# MY_beamControl_R.net
KiCad netlist of a schematic drawn in Altium Designer
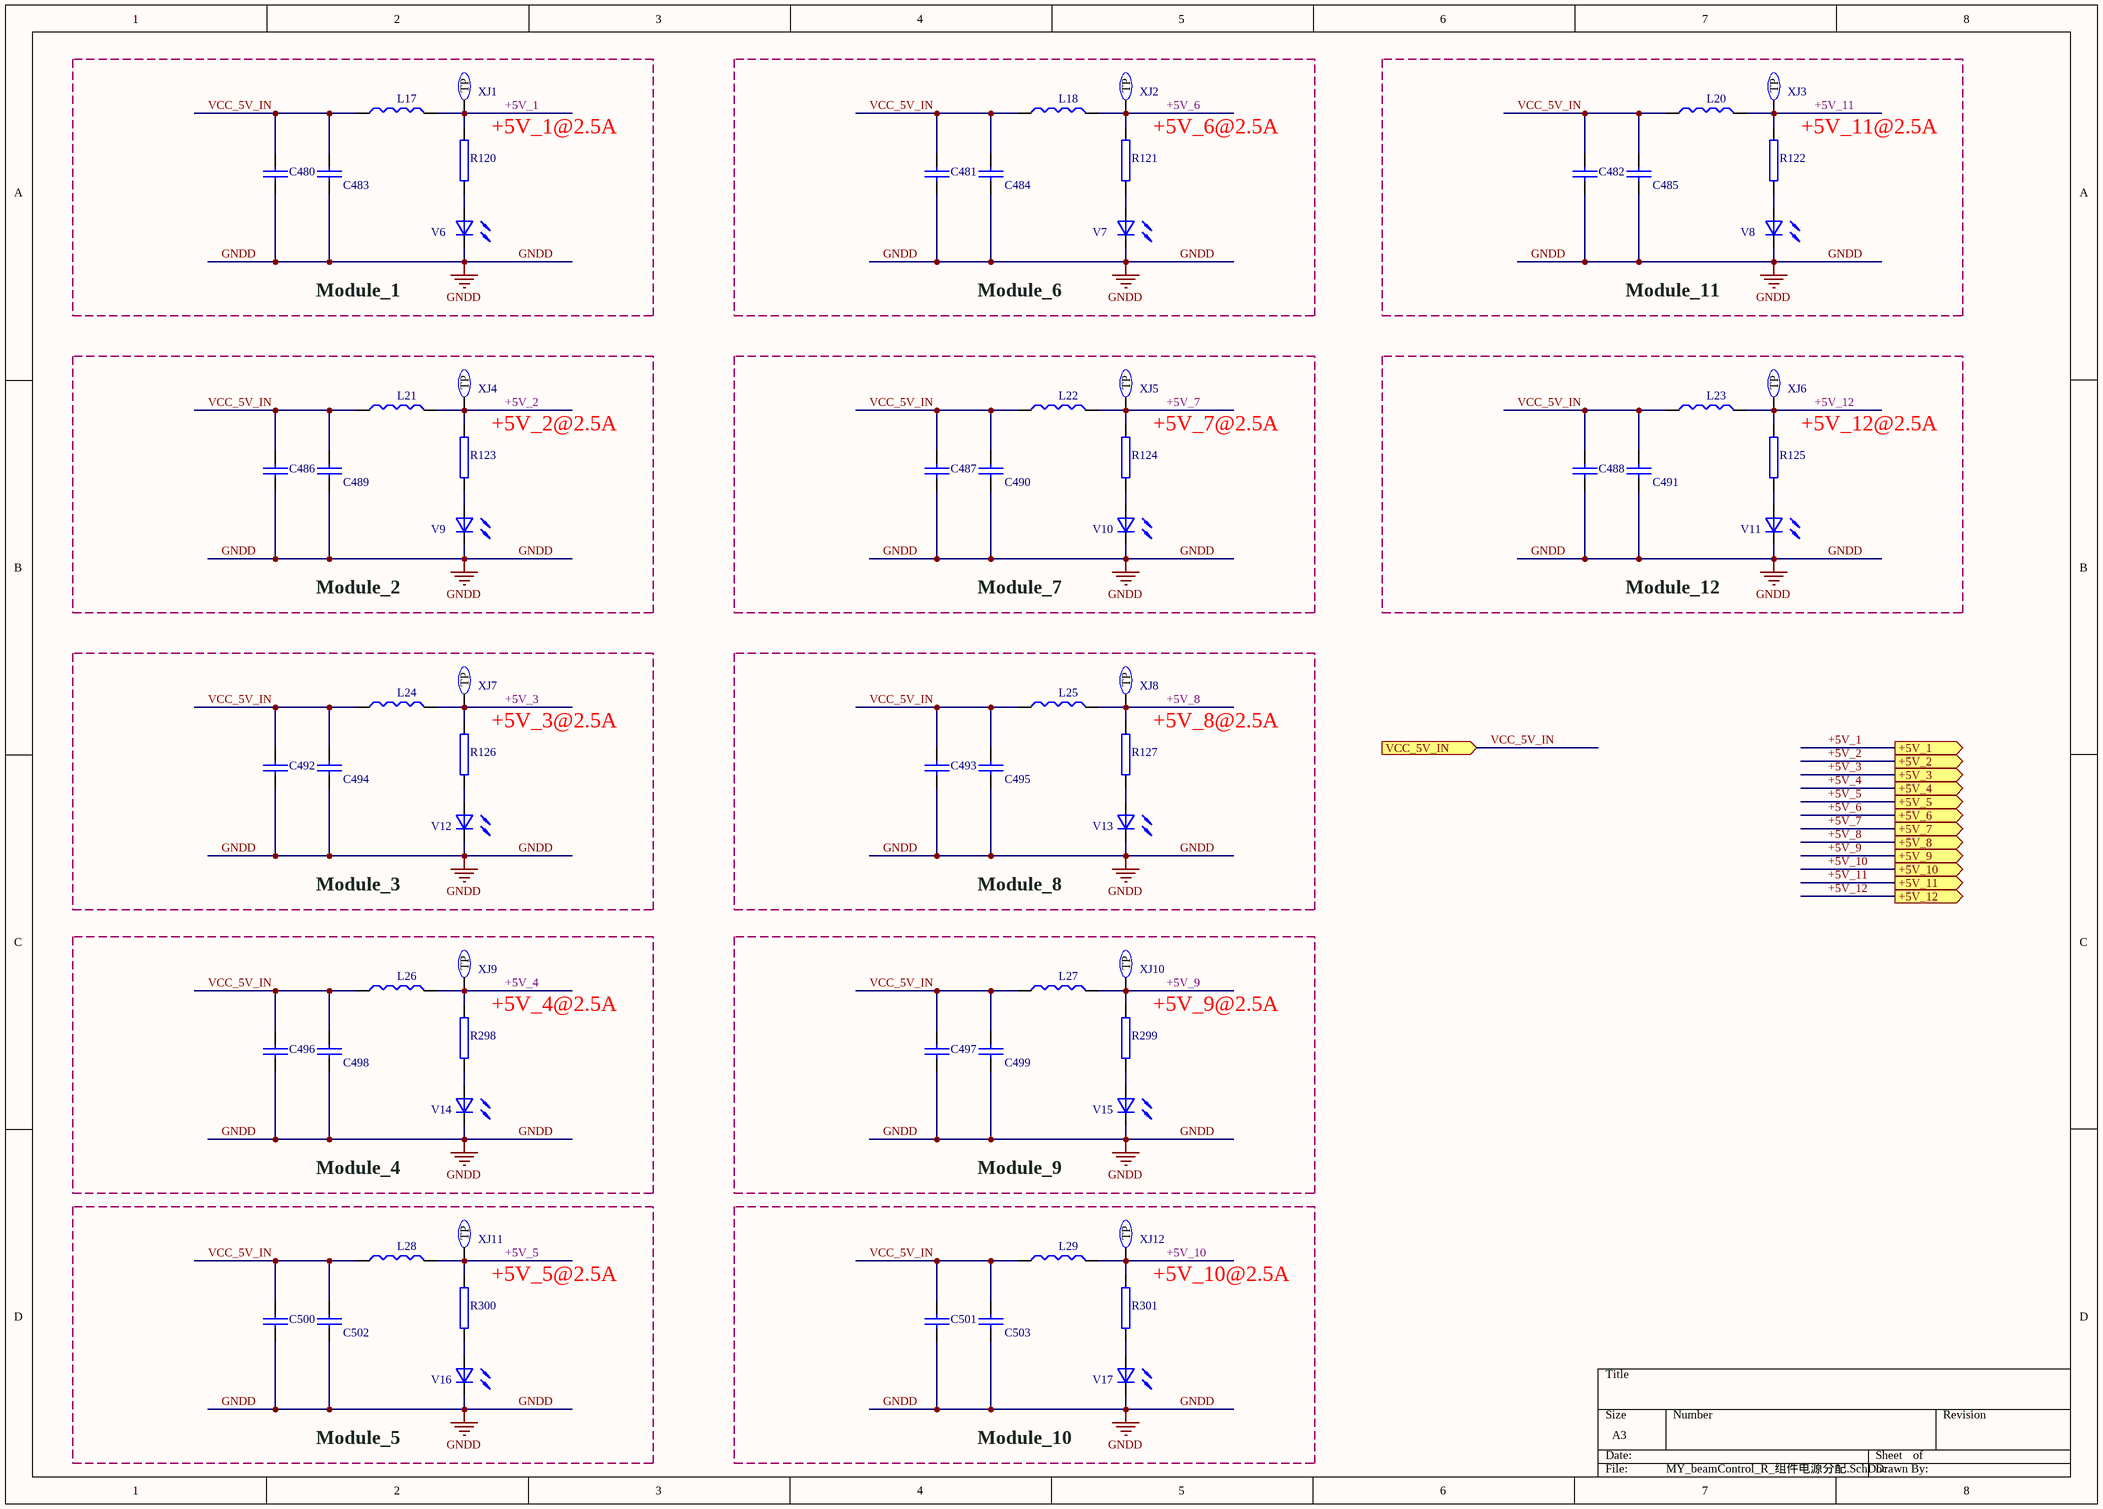
[diagram p0: MY_beamControl_R_组件电源分配.SchDoc]

(export (version "E")
  (design (tool "Eeschema 10.0.6"))
  (components
    (comp (ref "C480") (value "C0805-4.7uF/16V") (footprint "0805") (libsource (lib "mySchLib") (part "C")))
    (comp (ref "C481") (value "C0805-4.7uF/16V") (footprint "0805") (libsource (lib "mySchLib") (part "C")))
    (comp (ref "C482") (value "C0805-4.7uF/16V") (footprint "0805") (libsource (lib "mySchLib") (part "C")))
    (comp (ref "C483")
      (value "CT41-0402-2X1-16V-104(0.1μF)")
      (footprint "c0402")
      (libsource (lib "mySchLib") (part "C_2"))
    )
    (comp (ref "C484")
      (value "CT41-0402-2X1-16V-104(0.1μF)")
      (footprint "c0402")
      (libsource (lib "mySchLib") (part "C_2"))
    )
    (comp (ref "C485")
      (value "CT41-0402-2X1-16V-104(0.1μF)")
      (footprint "c0402")
      (libsource (lib "mySchLib") (part "C_2"))
    )
    (comp (ref "C486") (value "C0805-4.7uF/16V") (footprint "0805") (libsource (lib "mySchLib") (part "C")))
    (comp (ref "C487") (value "C0805-4.7uF/16V") (footprint "0805") (libsource (lib "mySchLib") (part "C")))
    (comp (ref "C488") (value "C0805-4.7uF/16V") (footprint "C0805") (libsource (lib "mySchLib") (part "C")))
    (comp (ref "C489")
      (value "CT41-0402-2X1-16V-104(0.1μF)")
      (footprint "c0402")
      (libsource (lib "mySchLib") (part "C_2"))
    )
    (comp (ref "C490")
      (value "CT41-0402-2X1-16V-104(0.1μF)")
      (footprint "c0402")
      (libsource (lib "mySchLib") (part "C_2"))
    )
    (comp (ref "C491")
      (value "CT41-0402-2X1-16V-104(0.1μF)")
      (footprint "c0402")
      (libsource (lib "mySchLib") (part "C_2"))
    )
    (comp (ref "C492") (value "C0805-4.7uF/16V") (footprint "0805") (libsource (lib "mySchLib") (part "C")))
    (comp (ref "C493") (value "C0805-4.7uF/16V") (footprint "0805") (libsource (lib "mySchLib") (part "C")))
    (comp (ref "C494")
      (value "CT41-0402-2X1-16V-104(0.1μF)")
      (footprint "c0402")
      (libsource (lib "mySchLib") (part "C_2"))
    )
    (comp (ref "C495")
      (value "CT41-0402-2X1-16V-104(0.1μF)")
      (footprint "c0402")
      (libsource (lib "mySchLib") (part "C_2"))
    )
    (comp (ref "C496") (value "C0805-4.7uF/16V") (footprint "0805") (libsource (lib "mySchLib") (part "C")))
    (comp (ref "C497") (value "C0805-4.7uF/16V") (footprint "0805") (libsource (lib "mySchLib") (part "C")))
    (comp (ref "C498")
      (value "CT41-0402-2X1-16V-104(0.1μF)")
      (footprint "c0402")
      (libsource (lib "mySchLib") (part "C_2"))
    )
    (comp (ref "C499")
      (value "CT41-0402-2X1-16V-104(0.1μF)")
      (footprint "c0402")
      (libsource (lib "mySchLib") (part "C_2"))
    )
    (comp (ref "C500") (value "C0805-4.7uF/16V") (footprint "0805") (libsource (lib "mySchLib") (part "C")))
    (comp (ref "C501") (value "C0805-4.7uF/16V") (footprint "0805") (libsource (lib "mySchLib") (part "C")))
    (comp (ref "C502")
      (value "CT41-0402-2X1-16V-104(0.1μF)")
      (footprint "c0402")
      (libsource (lib "mySchLib") (part "C_2"))
    )
    (comp (ref "C503")
      (value "CT41-0402-2X1-16V-104(0.1μF)")
      (footprint "c0402")
      (libsource (lib "mySchLib") (part "C_2"))
    )
    (comp (ref "L17")
      (value "MPZ2012S101A")
      (footprint "R0805")
      (libsource (lib "*") (part "ProE2A0.TMP_UnNamed_1"))
    )
    (comp (ref "L18")
      (value "MPZ2012S101A")
      (footprint "R0805")
      (libsource (lib "*") (part "ProE2A0.TMP_UnNamed_1"))
    )
    (comp (ref "L20")
      (value "MPZ2012S101A")
      (footprint "R0805")
      (libsource (lib "*") (part "ProE2A0.TMP_UnNamed_1"))
    )
    (comp (ref "L21")
      (value "MPZ2012S101A")
      (footprint "R0805")
      (libsource (lib "*") (part "ProE2A0.TMP_UnNamed_1"))
    )
    (comp (ref "L22")
      (value "MPZ2012S101A")
      (footprint "R0805")
      (libsource (lib "*") (part "ProE2A0.TMP_UnNamed_1"))
    )
    (comp (ref "L23")
      (value "MPZ2012S101A")
      (footprint "R0805")
      (libsource (lib "*") (part "ProE2A0.TMP_UnNamed_1"))
    )
    (comp (ref "L24")
      (value "MPZ2012S101A")
      (footprint "R0805")
      (libsource (lib "*") (part "ProE2A0.TMP_UnNamed_1"))
    )
    (comp (ref "L25")
      (value "MPZ2012S101A")
      (footprint "R0805")
      (libsource (lib "*") (part "ProE2A0.TMP_UnNamed_1"))
    )
    (comp (ref "L26")
      (value "MPZ2012S101A")
      (footprint "R0805")
      (libsource (lib "*") (part "ProE2A0.TMP_UnNamed_1"))
    )
    (comp (ref "L27")
      (value "MPZ2012S101A")
      (footprint "R0805")
      (libsource (lib "*") (part "ProE2A0.TMP_UnNamed_1"))
    )
    (comp (ref "L28")
      (value "MPZ2012S101A")
      (footprint "R0805")
      (libsource (lib "*") (part "ProE2A0.TMP_UnNamed_1"))
    )
    (comp (ref "L29")
      (value "MPZ2012S101A")
      (footprint "R0805")
      (libsource (lib "*") (part "ProE2A0.TMP_UnNamed_1"))
    )
    (comp (ref "R120") (value "0805-512(5.1K)") (footprint "0805") (libsource (lib "*") (part "RES2")))
    (comp (ref "R121") (value "0805-512(5.1K)") (footprint "0805") (libsource (lib "*") (part "RES2")))
    (comp (ref "R122") (value "0805-512(5.1K)") (footprint "0805") (libsource (lib "*") (part "RES2")))
    (comp (ref "R123") (value "0805-512(5.1K)") (footprint "0805") (libsource (lib "*") (part "RES2")))
    (comp (ref "R124") (value "0805-512(5.1K)") (footprint "0805") (libsource (lib "*") (part "RES2")))
    (comp (ref "R125") (value "0805-512(5.1K)") (footprint "0805") (libsource (lib "*") (part "RES2")))
    (comp (ref "R126") (value "0805-512(5.1K)") (footprint "0805") (libsource (lib "*") (part "RES2")))
    (comp (ref "R127") (value "0805-512(5.1K)") (footprint "0805") (libsource (lib "*") (part "RES2")))
    (comp (ref "R298") (value "0805-512(5.1K)") (footprint "0805") (libsource (lib "*") (part "RES2")))
    (comp (ref "R299") (value "0805-512(5.1K)") (footprint "0805") (libsource (lib "*") (part "RES2")))
    (comp (ref "R300") (value "0805-512(5.1K)") (footprint "0805") (libsource (lib "*") (part "RES2")))
    (comp (ref "R301") (value "0805-512(5.1K)") (footprint "0805") (libsource (lib "*") (part "RES2")))
    (comp (ref "V6") (value "LED0603-GREEN") (footprint "LED-R0603") (libsource (lib "*") (part "LED")))
    (comp (ref "V7") (value "LED0603-GREEN") (footprint "LED-R0603") (libsource (lib "*") (part "LED")))
    (comp (ref "V8") (value "LED0603-GREEN") (footprint "LED-R0603") (libsource (lib "*") (part "LED")))
    (comp (ref "V9") (value "LED0603-GREEN") (footprint "LED-R0603") (libsource (lib "*") (part "LED")))
    (comp (ref "V10") (value "LED0603-GREEN") (footprint "LED-R0603") (libsource (lib "*") (part "LED")))
    (comp (ref "V11") (value "LED0603-GREEN") (footprint "LED-R0603") (libsource (lib "*") (part "LED")))
    (comp (ref "V12") (value "LED0603-GREEN") (footprint "LED-R0603") (libsource (lib "*") (part "LED")))
    (comp (ref "V13") (value "LED0603-GREEN") (footprint "LED-R0603") (libsource (lib "*") (part "LED")))
    (comp (ref "V14") (value "LED0603-GREEN") (footprint "LED-R0603") (libsource (lib "*") (part "LED")))
    (comp (ref "V15") (value "LED0603-GREEN") (footprint "LED-R0603") (libsource (lib "*") (part "LED")))
    (comp (ref "V16") (value "LED0603-GREEN") (footprint "LED-R0603") (libsource (lib "*") (part "LED")))
    (comp (ref "V17") (value "LED0603-GREEN") (footprint "LED-R0603") (libsource (lib "*") (part "LED")))
    (comp (ref "XJ1")
      (value "Test Point")
      (footprint "TP3")
      (description "测试点")
      (libsource (lib "mySchLib") (part "TP"))
    )
    (comp (ref "XJ2")
      (value "Test Point")
      (footprint "TP3")
      (description "测试点")
      (libsource (lib "mySchLib") (part "TP"))
    )
    (comp (ref "XJ3")
      (value "Test Point")
      (footprint "TP3")
      (description "测试点")
      (libsource (lib "mySchLib") (part "TP"))
    )
    (comp (ref "XJ4")
      (value "Test Point")
      (footprint "TP3")
      (description "测试点")
      (libsource (lib "mySchLib") (part "TP"))
    )
    (comp (ref "XJ5")
      (value "Test Point")
      (footprint "TP3")
      (description "测试点")
      (libsource (lib "mySchLib") (part "TP"))
    )
    (comp (ref "XJ6")
      (value "Test Point")
      (footprint "TP3")
      (description "测试点")
      (libsource (lib "mySchLib") (part "TP"))
    )
    (comp (ref "XJ7")
      (value "Test Point")
      (footprint "TP3")
      (description "测试点")
      (libsource (lib "mySchLib") (part "TP"))
    )
    (comp (ref "XJ8")
      (value "Test Point")
      (footprint "TP3")
      (description "测试点")
      (libsource (lib "mySchLib") (part "TP"))
    )
    (comp (ref "XJ9")
      (value "Test Point")
      (footprint "TP3")
      (description "测试点")
      (libsource (lib "mySchLib") (part "TP"))
    )
    (comp (ref "XJ10")
      (value "Test Point")
      (footprint "TP3")
      (description "测试点")
      (libsource (lib "mySchLib") (part "TP"))
    )
    (comp (ref "XJ11")
      (value "Test Point")
      (footprint "TP3")
      (description "测试点")
      (libsource (lib "mySchLib") (part "TP"))
    )
    (comp (ref "XJ12")
      (value "Test Point")
      (footprint "TP3")
      (description "测试点")
      (libsource (lib "mySchLib") (part "TP"))
    )
  )
  (nets
    (net (code "1") (name "/+5V_1") (class "Default")
      (node (ref "L17") (pin "2") (pintype "passive"))
      (node (ref "R120") (pin "2") (pintype "passive"))
      (node (ref "XJ1") (pin "1") (pinfunction "TP_1") (pintype "passive"))
    )
    (net (code "2") (name "/+5V_2") (class "Default")
      (node (ref "L21") (pin "2") (pintype "passive"))
      (node (ref "R123") (pin "2") (pintype "passive"))
      (node (ref "XJ4") (pin "1") (pinfunction "TP_1") (pintype "passive"))
    )
    (net (code "3") (name "/+5V_3") (class "Default")
      (node (ref "L24") (pin "2") (pintype "passive"))
      (node (ref "R126") (pin "2") (pintype "passive"))
      (node (ref "XJ7") (pin "1") (pinfunction "TP_1") (pintype "passive"))
    )
    (net (code "4") (name "/+5V_4") (class "Default")
      (node (ref "L26") (pin "2") (pintype "passive"))
      (node (ref "R298") (pin "2") (pintype "passive"))
      (node (ref "XJ9") (pin "1") (pinfunction "TP_1") (pintype "passive"))
    )
    (net (code "5") (name "/+5V_5") (class "Default")
      (node (ref "L28") (pin "2") (pintype "passive"))
      (node (ref "R300") (pin "2") (pintype "passive"))
      (node (ref "XJ11") (pin "1") (pinfunction "TP_1") (pintype "passive"))
    )
    (net (code "6") (name "/+5V_6") (class "Default")
      (node (ref "L18") (pin "2") (pintype "passive"))
      (node (ref "R121") (pin "2") (pintype "passive"))
      (node (ref "XJ2") (pin "1") (pinfunction "TP_1") (pintype "passive"))
    )
    (net (code "7") (name "/+5V_7") (class "Default")
      (node (ref "L22") (pin "2") (pintype "passive"))
      (node (ref "R124") (pin "2") (pintype "passive"))
      (node (ref "XJ5") (pin "1") (pinfunction "TP_1") (pintype "passive"))
    )
    (net (code "8") (name "/+5V_8") (class "Default")
      (node (ref "L25") (pin "2") (pintype "passive"))
      (node (ref "R127") (pin "2") (pintype "passive"))
      (node (ref "XJ8") (pin "1") (pinfunction "TP_1") (pintype "passive"))
    )
    (net (code "9") (name "/+5V_9") (class "Default")
      (node (ref "L27") (pin "2") (pintype "passive"))
      (node (ref "R299") (pin "2") (pintype "passive"))
      (node (ref "XJ10") (pin "1") (pinfunction "TP_1") (pintype "passive"))
    )
    (net (code "10") (name "/+5V_10") (class "Default")
      (node (ref "L29") (pin "2") (pintype "passive"))
      (node (ref "R301") (pin "2") (pintype "passive"))
      (node (ref "XJ12") (pin "1") (pinfunction "TP_1") (pintype "passive"))
    )
    (net (code "11") (name "/+5V_11") (class "Default")
      (node (ref "L20") (pin "2") (pintype "passive"))
      (node (ref "R122") (pin "2") (pintype "passive"))
      (node (ref "XJ3") (pin "1") (pinfunction "TP_1") (pintype "passive"))
    )
    (net (code "12") (name "/+5V_12") (class "Default")
      (node (ref "L23") (pin "2") (pintype "passive"))
      (node (ref "R125") (pin "2") (pintype "passive"))
      (node (ref "XJ6") (pin "1") (pinfunction "TP_1") (pintype "passive"))
    )
    (net (code "13") (name "/VCC_5V_IN") (class "Default")
      (node (ref "C480") (pin "2") (pintype "passive"))
      (node (ref "C481") (pin "2") (pintype "passive"))
      (node (ref "C482") (pin "2") (pintype "passive"))
      (node (ref "C483") (pin "1") (pintype "passive"))
      (node (ref "C484") (pin "1") (pintype "passive"))
      (node (ref "C485") (pin "1") (pintype "passive"))
      (node (ref "C486") (pin "2") (pintype "passive"))
      (node (ref "C487") (pin "2") (pintype "passive"))
      (node (ref "C488") (pin "2") (pintype "passive"))
      (node (ref "C489") (pin "1") (pintype "passive"))
      (node (ref "C490") (pin "1") (pintype "passive"))
      (node (ref "C491") (pin "1") (pintype "passive"))
      (node (ref "C492") (pin "2") (pintype "passive"))
      (node (ref "C493") (pin "2") (pintype "passive"))
      (node (ref "C494") (pin "1") (pintype "passive"))
      (node (ref "C495") (pin "1") (pintype "passive"))
      (node (ref "C496") (pin "2") (pintype "passive"))
      (node (ref "C497") (pin "2") (pintype "passive"))
      (node (ref "C498") (pin "1") (pintype "passive"))
      (node (ref "C499") (pin "1") (pintype "passive"))
      (node (ref "C500") (pin "2") (pintype "passive"))
      (node (ref "C501") (pin "2") (pintype "passive"))
      (node (ref "C502") (pin "1") (pintype "passive"))
      (node (ref "C503") (pin "1") (pintype "passive"))
      (node (ref "L17") (pin "1") (pintype "passive"))
      (node (ref "L18") (pin "1") (pintype "passive"))
      (node (ref "L20") (pin "1") (pintype "passive"))
      (node (ref "L21") (pin "1") (pintype "passive"))
      (node (ref "L22") (pin "1") (pintype "passive"))
      (node (ref "L23") (pin "1") (pintype "passive"))
      (node (ref "L24") (pin "1") (pintype "passive"))
      (node (ref "L25") (pin "1") (pintype "passive"))
      (node (ref "L26") (pin "1") (pintype "passive"))
      (node (ref "L27") (pin "1") (pintype "passive"))
      (node (ref "L28") (pin "1") (pintype "passive"))
      (node (ref "L29") (pin "1") (pintype "passive"))
    )
    (net (code "14") (name "GNDD") (class "Default")
      (node (ref "C480") (pin "1") (pintype "passive"))
      (node (ref "C481") (pin "1") (pintype "passive"))
      (node (ref "C482") (pin "1") (pintype "passive"))
      (node (ref "C483") (pin "2") (pintype "passive"))
      (node (ref "C484") (pin "2") (pintype "passive"))
      (node (ref "C485") (pin "2") (pintype "passive"))
      (node (ref "C486") (pin "1") (pintype "passive"))
      (node (ref "C487") (pin "1") (pintype "passive"))
      (node (ref "C488") (pin "1") (pintype "passive"))
      (node (ref "C489") (pin "2") (pintype "passive"))
      (node (ref "C490") (pin "2") (pintype "passive"))
      (node (ref "C491") (pin "2") (pintype "passive"))
      (node (ref "C492") (pin "1") (pintype "passive"))
      (node (ref "C493") (pin "1") (pintype "passive"))
      (node (ref "C494") (pin "2") (pintype "passive"))
      (node (ref "C495") (pin "2") (pintype "passive"))
      (node (ref "C496") (pin "1") (pintype "passive"))
      (node (ref "C497") (pin "1") (pintype "passive"))
      (node (ref "C498") (pin "2") (pintype "passive"))
      (node (ref "C499") (pin "2") (pintype "passive"))
      (node (ref "C500") (pin "1") (pintype "passive"))
      (node (ref "C501") (pin "1") (pintype "passive"))
      (node (ref "C502") (pin "2") (pintype "passive"))
      (node (ref "C503") (pin "2") (pintype "passive"))
      (node (ref "V10") (pin "2") (pinfunction "K_2") (pintype "passive"))
      (node (ref "V11") (pin "2") (pinfunction "K_2") (pintype "passive"))
      (node (ref "V12") (pin "2") (pinfunction "K_2") (pintype "passive"))
      (node (ref "V13") (pin "2") (pinfunction "K_2") (pintype "passive"))
      (node (ref "V14") (pin "2") (pinfunction "K_2") (pintype "passive"))
      (node (ref "V15") (pin "2") (pinfunction "K_2") (pintype "passive"))
      (node (ref "V16") (pin "2") (pinfunction "K_2") (pintype "passive"))
      (node (ref "V17") (pin "2") (pinfunction "K_2") (pintype "passive"))
      (node (ref "V6") (pin "2") (pinfunction "K_2") (pintype "passive"))
      (node (ref "V7") (pin "2") (pinfunction "K_2") (pintype "passive"))
      (node (ref "V8") (pin "2") (pinfunction "K_2") (pintype "passive"))
      (node (ref "V9") (pin "2") (pinfunction "K_2") (pintype "passive"))
    )
    (net (code "15") (name "Net-(V6-A)") (class "Default")
      (node (ref "R120") (pin "1") (pintype "passive"))
      (node (ref "V6") (pin "1") (pinfunction "A_1") (pintype "passive"))
    )
    (net (code "16") (name "Net-(V7-A)") (class "Default")
      (node (ref "R121") (pin "1") (pintype "passive"))
      (node (ref "V7") (pin "1") (pinfunction "A_1") (pintype "passive"))
    )
    (net (code "17") (name "Net-(V8-A)") (class "Default")
      (node (ref "R122") (pin "1") (pintype "passive"))
      (node (ref "V8") (pin "1") (pinfunction "A_1") (pintype "passive"))
    )
    (net (code "18") (name "Net-(V9-A)") (class "Default")
      (node (ref "R123") (pin "1") (pintype "passive"))
      (node (ref "V9") (pin "1") (pinfunction "A_1") (pintype "passive"))
    )
    (net (code "19") (name "Net-(V10-A)") (class "Default")
      (node (ref "R124") (pin "1") (pintype "passive"))
      (node (ref "V10") (pin "1") (pinfunction "A_1") (pintype "passive"))
    )
    (net (code "20") (name "Net-(V11-A)") (class "Default")
      (node (ref "R125") (pin "1") (pintype "passive"))
      (node (ref "V11") (pin "1") (pinfunction "A_1") (pintype "passive"))
    )
    (net (code "21") (name "Net-(V12-A)") (class "Default")
      (node (ref "R126") (pin "1") (pintype "passive"))
      (node (ref "V12") (pin "1") (pinfunction "A_1") (pintype "passive"))
    )
    (net (code "22") (name "Net-(V13-A)") (class "Default")
      (node (ref "R127") (pin "1") (pintype "passive"))
      (node (ref "V13") (pin "1") (pinfunction "A_1") (pintype "passive"))
    )
    (net (code "23") (name "Net-(V14-A)") (class "Default")
      (node (ref "R298") (pin "1") (pintype "passive"))
      (node (ref "V14") (pin "1") (pinfunction "A_1") (pintype "passive"))
    )
    (net (code "24") (name "Net-(V15-A)") (class "Default")
      (node (ref "R299") (pin "1") (pintype "passive"))
      (node (ref "V15") (pin "1") (pinfunction "A_1") (pintype "passive"))
    )
    (net (code "25") (name "Net-(V16-A)") (class "Default")
      (node (ref "R300") (pin "1") (pintype "passive"))
      (node (ref "V16") (pin "1") (pinfunction "A_1") (pintype "passive"))
    )
    (net (code "26") (name "Net-(V17-A)") (class "Default")
      (node (ref "R301") (pin "1") (pintype "passive"))
      (node (ref "V17") (pin "1") (pinfunction "A_1") (pintype "passive"))
    )
  )
)
